# openSX70_WIP_NEW_LAYOUT_20171230_V32_man.net
KiCad netlist of a schematic drawn in EAGLE
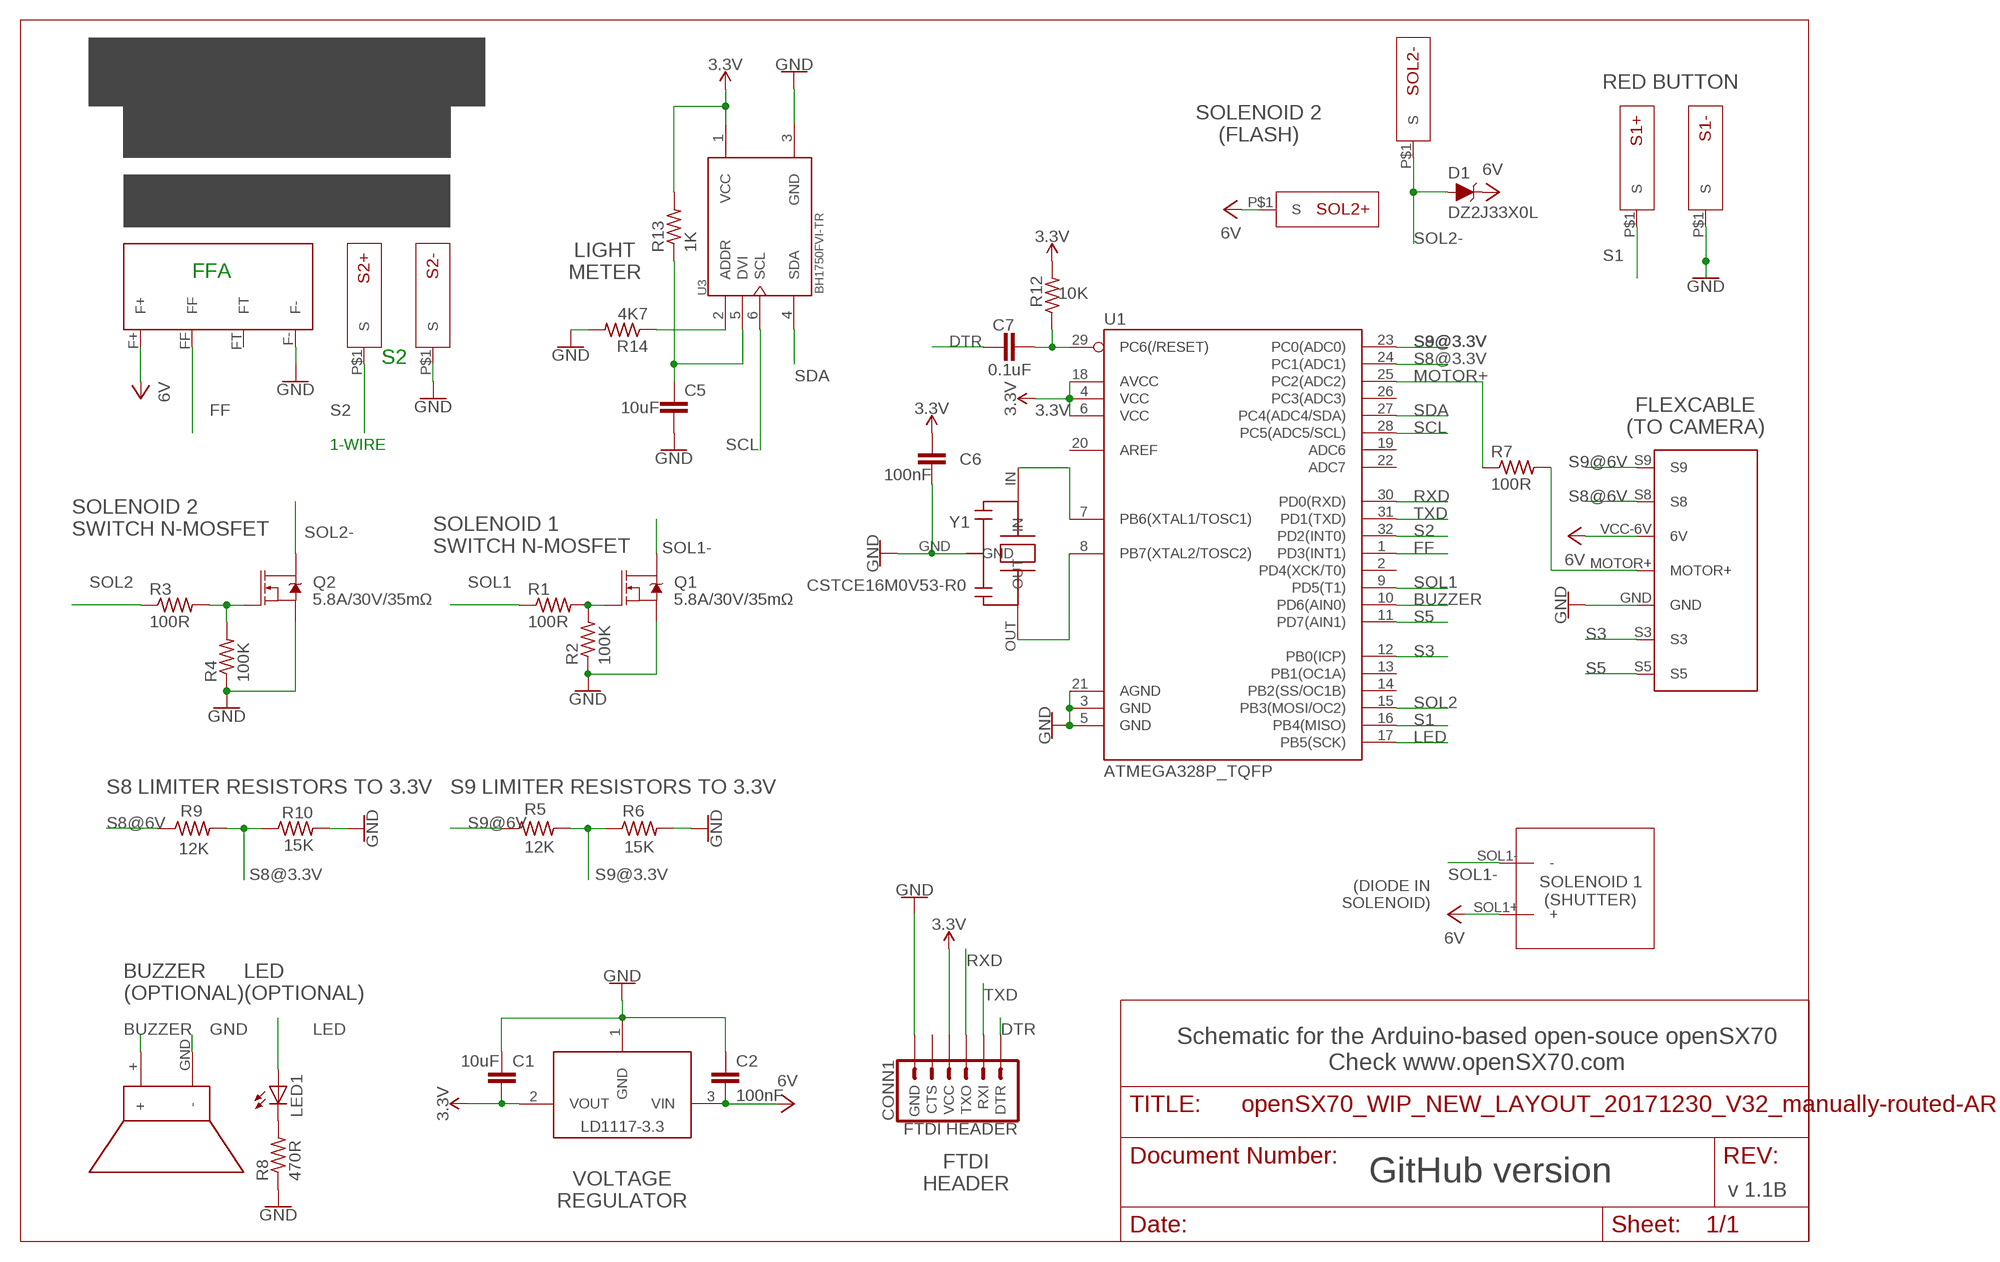
[diagram p0: schematic, sheet 1]

(export (version "E")
  (design (tool "Eeschema 10.0.6"))
  (components
    (comp (ref "BUZZ1")
      (value "CSET8-5G")
      (footprint "eagle-import:CSET8-5G_PACKAGE")
      (libsource (lib "eagle-import") (part "CSET8-5G"))
    )
    (comp (ref "C1")
      (value "10uF")
      (footprint "eagle-import:0603")
      (libsource (lib "eagle-import") (part "10UF-0603-6.3V-20%"))
    )
    (comp (ref "C2")
      (value "100nF")
      (footprint "eagle-import:C0603K")
      (libsource (lib "eagle-import") (part "C-EUC0603K"))
    )
    (comp (ref "C5")
      (value "10uF")
      (footprint "eagle-import:0603")
      (libsource (lib "eagle-import") (part "10UF-0603-6.3V-20%"))
    )
    (comp (ref "C6")
      (value "100nF")
      (footprint "eagle-import:C0805")
      (libsource (lib "eagle-import") (part "resistor_C-EUC0805"))
    )
    (comp (ref "C7")
      (value "0.1uF")
      (footprint "eagle-import:0603")
      (libsource (lib "eagle-import") (part "0.1UF-0603-25V-(+80/-20%)"))
    )
    (comp (ref "CONN1")
      (value "FTDI HEADER")
      (footprint "eagle-import:1X06")
      (libsource (lib "eagle-import") (part "6_PIN_SERIAL_TARGET"))
    )
    (comp (ref "D1")
      (value "DZ2J33X0L")
      (footprint "eagle-import:SMINI2")
      (libsource (lib "eagle-import") (part "DZ2J33X0L"))
    )
    (comp (ref "LD11173.3V")
      (value "LD1117 3.3V")
      (footprint "eagle-import:SOT223")
      (fields (field (name "MF") "Advanced Monolithic Systems") (field (name "MP") "AMS1117-5.0"))
      (libsource (lib "eagle-import") (part "LD1117-3.3"))
    )
    (comp (ref "LED1")
      (value "LEDCHIPLED_0805")
      (footprint "eagle-import:CHIPLED_0805")
      (libsource (lib "eagle-import") (part "LEDCHIPLED_0805"))
    )
    (comp (ref "Q1")
      (value "5.8A/30V/35mΩ")
      (footprint "eagle-import:SOT23-3")
      (libsource (lib "eagle-import") (part "MOSFET-NCH-AO3404A"))
    )
    (comp (ref "Q2")
      (value "5.8A/30V/35mΩ")
      (footprint "eagle-import:SOT23-3")
      (libsource (lib "eagle-import") (part "MOSFET-NCH-AO3404A"))
    )
    (comp (ref "R1")
      (value "100R")
      (footprint "eagle-import:R0603")
      (libsource (lib "eagle-import") (part "R-US_R0603"))
    )
    (comp (ref "R2")
      (value "100K")
      (footprint "eagle-import:R0603")
      (libsource (lib "eagle-import") (part "R-US_R0603"))
    )
    (comp (ref "R3")
      (value "100R")
      (footprint "eagle-import:R0603")
      (libsource (lib "eagle-import") (part "R-US_R0603"))
    )
    (comp (ref "R4")
      (value "100K")
      (footprint "eagle-import:R0603")
      (libsource (lib "eagle-import") (part "R-US_R0603"))
    )
    (comp (ref "R5")
      (value "12K")
      (footprint "eagle-import:R0603")
      (libsource (lib "eagle-import") (part "R-US_R0603"))
    )
    (comp (ref "R6")
      (value "15K")
      (footprint "eagle-import:R0603")
      (libsource (lib "eagle-import") (part "R-US_R0603"))
    )
    (comp (ref "R7")
      (value "100R")
      (footprint "eagle-import:R0603")
      (libsource (lib "eagle-import") (part "R-US_R0603"))
    )
    (comp (ref "R8")
      (value "470R")
      (footprint "eagle-import:R0603")
      (libsource (lib "eagle-import") (part "R-US_R0603"))
    )
    (comp (ref "R9")
      (value "12K")
      (footprint "eagle-import:R0603")
      (libsource (lib "eagle-import") (part "R-US_R0603"))
    )
    (comp (ref "R10")
      (value "15K")
      (footprint "eagle-import:R0603")
      (libsource (lib "eagle-import") (part "R-US_R0603"))
    )
    (comp (ref "R12")
      (value "10K")
      (footprint "eagle-import:R0603")
      (libsource (lib "eagle-import") (part "R-US_R0603"))
    )
    (comp (ref "R13")
      (value "1K")
      (footprint "eagle-import:R0603")
      (libsource (lib "eagle-import") (part "R-US_R0603"))
    )
    (comp (ref "R14")
      (value "4K7")
      (footprint "eagle-import:R0603")
      (libsource (lib "eagle-import") (part "R-US_R0603"))
    )
    (comp (ref "S1+")
      (value "SX70-S-PAD-NEW")
      (footprint "eagle-import:SX70-S-PAD2")
      (libsource (lib "eagle-import") (part "SX70-S-PAD-NEW"))
    )
    (comp (ref "S1-")
      (value "SX70-S-PAD-NEW")
      (footprint "eagle-import:SX70-S-PAD2")
      (libsource (lib "eagle-import") (part "SX70-S-PAD-NEW"))
    )
    (comp (ref "S2+")
      (value "SX70-S-PAD-NEW")
      (footprint "eagle-import:SX70-S-PAD2")
      (libsource (lib "eagle-import") (part "SX70-S-PAD-NEW"))
    )
    (comp (ref "S2-")
      (value "SX70-S-PAD-NEW")
      (footprint "eagle-import:SX70-S-PAD2")
      (libsource (lib "eagle-import") (part "SX70-S-PAD-NEW"))
    )
    (comp (ref "SOL1")
      (value "SX70-SOLENOID1-2PADS")
      (footprint "eagle-import:SX70-SOLENOID1-2")
      (libsource (lib "eagle-import") (part "SX70-SOLENOID1-2PADS"))
    )
    (comp (ref "SOL2+")
      (value "SX70-S-PAD-NEW")
      (footprint "eagle-import:SX70-S-PAD2")
      (libsource (lib "eagle-import") (part "SX70-S-PAD-NEW"))
    )
    (comp (ref "SOL2-")
      (value "SX70-S-PAD-NEW")
      (footprint "eagle-import:SX70-S-PAD2")
      (libsource (lib "eagle-import") (part "SX70-S-PAD-NEW"))
    )
    (comp (ref "U$1")
      (value "SX70-7-PAD")
      (footprint "eagle-import:SX70-7-PAD")
      (libsource (lib "eagle-import") (part "SX70-7-PAD"))
    )
    (comp (ref "U$2")
      (value "FFA")
      (footprint "eagle-import:FFA-PAD-PACKAGE")
      (libsource (lib "eagle-import") (part "SX70-FFA-PAD"))
    )
    (comp (ref "U1")
      (value "ATMEGA328P_TQFP")
      (footprint "eagle-import:TQFP32-08")
      (libsource (lib "eagle-import") (part "ATMEGA328P_TQFP"))
    )
    (comp (ref "U3")
      (value "BH1750FVI-TR")
      (footprint "eagle-import:SOTFL50P300X75-6N")
      (fields (field (name "MF") "Rohm"))
      (libsource (lib "eagle-import") (part "BH1750FVI-TR"))
    )
    (comp (ref "Y1")
      (value "CSTCE16M0V53-R0")
      (footprint "eagle-import:CFP95P160X100-3N")
      (fields (field (name "MF") "Murata"))
      (libsource (lib "eagle-import") (part "CSTCE16M0V53-R0"))
    )
  )
  (nets
    (net (code "1") (name "/BUZZER") (class "Default")
      (node (ref "BUZZ1") (pin "+") (pinfunction "+_+") (pintype "bidirectional"))
      (node (ref "U1") (pin "10") (pinfunction "PD6(AIN0)_10") (pintype "bidirectional"))
    )
    (net (code "2") (name "/DTR") (class "Default")
      (node (ref "C7") (pin "1") (pinfunction "1_1") (pintype "passive"))
      (node (ref "CONN1") (pin "1") (pinfunction "DTR_1") (pintype "passive"))
    )
    (net (code "3") (name "/FF") (class "Default")
      (node (ref "U$2") (pin "FF") (pinfunction "FF_FF") (pintype "bidirectional"))
      (node (ref "U1") (pin "1") (pinfunction "PD3(INT1)_1") (pintype "bidirectional"))
    )
    (net (code "4") (name "/LED") (class "Default")
      (node (ref "LED1") (pin "A") (pinfunction "A_A") (pintype "passive"))
      (node (ref "U1") (pin "17") (pinfunction "PB5(SCK)_17") (pintype "bidirectional"))
    )
    (net (code "5") (name "/MOTOR+") (class "Default")
      (node (ref "R7") (pin "1") (pinfunction "1_1") (pintype "passive"))
      (node (ref "U1") (pin "25") (pinfunction "PC2(ADC2)_25") (pintype "bidirectional"))
    )
    (net (code "6") (name "/RXD") (class "Default")
      (node (ref "CONN1") (pin "3") (pinfunction "TXO_3") (pintype "passive"))
      (node (ref "U1") (pin "30") (pinfunction "PD0(RXD)_30") (pintype "bidirectional"))
    )
    (net (code "7") (name "/S1") (class "Default")
      (node (ref "S1+") (pin "P$1") (pinfunction "S_P$1") (pintype "bidirectional"))
      (node (ref "U1") (pin "16") (pinfunction "PB4(MISO)_16") (pintype "bidirectional"))
    )
    (net (code "8") (name "/S2") (class "Default")
      (node (ref "S2+") (pin "P$1") (pinfunction "S_P$1") (pintype "bidirectional"))
      (node (ref "U1") (pin "32") (pinfunction "PD2(INT0)_32") (pintype "bidirectional"))
    )
    (net (code "9") (name "/S3") (class "Default")
      (node (ref "U$1") (pin "S3") (pinfunction "S3_S3") (pintype "bidirectional"))
      (node (ref "U1") (pin "12") (pinfunction "PB0(ICP)_12") (pintype "bidirectional"))
    )
    (net (code "10") (name "/S5") (class "Default")
      (node (ref "U$1") (pin "S5") (pinfunction "S5_S5") (pintype "bidirectional"))
      (node (ref "U1") (pin "11") (pinfunction "PD7(AIN1)_11") (pintype "bidirectional"))
    )
    (net (code "11") (name "/S8@3.3V") (class "Default")
      (node (ref "R10") (pin "1") (pinfunction "1_1") (pintype "passive"))
      (node (ref "R9") (pin "2") (pinfunction "2_2") (pintype "passive"))
      (node (ref "U1") (pin "24") (pinfunction "PC1(ADC1)_24") (pintype "bidirectional"))
    )
    (net (code "12") (name "/S8@6V") (class "Default")
      (node (ref "R9") (pin "1") (pinfunction "1_1") (pintype "passive"))
      (node (ref "U$1") (pin "S8") (pinfunction "S8_S8") (pintype "bidirectional"))
    )
    (net (code "13") (name "/S9@3.3V") (class "Default")
      (node (ref "R5") (pin "2") (pinfunction "2_2") (pintype "passive"))
      (node (ref "R6") (pin "1") (pinfunction "1_1") (pintype "passive"))
      (node (ref "U1") (pin "23") (pinfunction "PC0(ADC0)_23") (pintype "bidirectional"))
    )
    (net (code "14") (name "/S9@6V") (class "Default")
      (node (ref "R5") (pin "1") (pinfunction "1_1") (pintype "passive"))
      (node (ref "U$1") (pin "S9") (pinfunction "S9_S9") (pintype "bidirectional"))
    )
    (net (code "15") (name "/SCL") (class "Default")
      (node (ref "U1") (pin "28") (pinfunction "PC5(ADC5/SCL)_28") (pintype "bidirectional"))
      (node (ref "U3") (pin "6") (pinfunction "SCL_6") (pintype "input"))
    )
    (net (code "16") (name "/SDA") (class "Default")
      (node (ref "U1") (pin "27") (pinfunction "PC4(ADC4/SDA)_27") (pintype "bidirectional"))
      (node (ref "U3") (pin "4") (pinfunction "SDA_4") (pintype "bidirectional"))
    )
    (net (code "17") (name "/SOL1") (class "Default")
      (node (ref "R1") (pin "1") (pinfunction "1_1") (pintype "passive"))
      (node (ref "U1") (pin "9") (pinfunction "PD5(T1)_9") (pintype "bidirectional"))
    )
    (net (code "18") (name "/SOL1-") (class "Default")
      (node (ref "Q1") (pin "3") (pinfunction "D_3") (pintype "bidirectional"))
      (node (ref "SOL1") (pin "SOL1-") (pinfunction "-_SOL1-") (pintype "bidirectional"))
    )
    (net (code "19") (name "/SOL2") (class "Default")
      (node (ref "R3") (pin "1") (pinfunction "1_1") (pintype "passive"))
      (node (ref "U1") (pin "15") (pinfunction "PB3(MOSI/OC2)_15") (pintype "bidirectional"))
    )
    (net (code "20") (name "/SOL2-") (class "Default")
      (node (ref "D1") (pin "P$2") (pinfunction "A_P$2") (pintype "passive"))
      (node (ref "Q2") (pin "3") (pinfunction "D_3") (pintype "bidirectional"))
      (node (ref "SOL2-") (pin "P$1") (pinfunction "S_P$1") (pintype "bidirectional"))
    )
    (net (code "21") (name "/TXD") (class "Default")
      (node (ref "CONN1") (pin "2") (pinfunction "RXI_2") (pintype "passive"))
      (node (ref "U1") (pin "31") (pinfunction "PD1(TXD)_31") (pintype "bidirectional"))
    )
    (net (code "22") (name "3.3V") (class "Default")
      (node (ref "C1") (pin "2") (pinfunction "2_2") (pintype "passive"))
      (node (ref "C6") (pin "1") (pinfunction "1_1") (pintype "passive"))
      (node (ref "CONN1") (pin "4") (pinfunction "VCC_4") (pintype "passive"))
      (node (ref "LD11173.3V") (pin "2") (pinfunction "VOUT_2") (pintype "bidirectional"))
      (node (ref "R12") (pin "2") (pinfunction "2_2") (pintype "passive"))
      (node (ref "R13") (pin "2") (pinfunction "2_2") (pintype "passive"))
      (node (ref "U1") (pin "18") (pinfunction "AVCC_18") (pintype "bidirectional"))
      (node (ref "U1") (pin "4") (pinfunction "VCC_4") (pintype "bidirectional"))
      (node (ref "U1") (pin "6") (pinfunction "VCC_6") (pintype "bidirectional"))
      (node (ref "U3") (pin "1") (pinfunction "VCC_1") (pintype "power_in"))
    )
    (net (code "23") (name "6V") (class "Default")
      (node (ref "C2") (pin "2") (pinfunction "2_2") (pintype "passive"))
      (node (ref "D1") (pin "P$1") (pinfunction "C_P$1") (pintype "passive"))
      (node (ref "LD11173.3V") (pin "3") (pinfunction "VIN_3") (pintype "bidirectional"))
      (node (ref "SOL1") (pin "SOL1+") (pinfunction "+_SOL1+") (pintype "bidirectional"))
      (node (ref "SOL2+") (pin "P$1") (pinfunction "S_P$1") (pintype "bidirectional"))
      (node (ref "U$1") (pin "VCC-6V") (pinfunction "6V_VCC-6V") (pintype "bidirectional"))
      (node (ref "U$2") (pin "F+") (pinfunction "F+_F+") (pintype "bidirectional"))
    )
    (net (code "24") (name "GND") (class "Default")
      (node (ref "BUZZ1") (pin "GND") (pinfunction "-_GND") (pintype "bidirectional"))
      (node (ref "C1") (pin "1") (pinfunction "1_1") (pintype "passive"))
      (node (ref "C2") (pin "1") (pinfunction "1_1") (pintype "passive"))
      (node (ref "C5") (pin "2") (pinfunction "2_2") (pintype "passive"))
      (node (ref "C6") (pin "2") (pinfunction "2_2") (pintype "passive"))
      (node (ref "CONN1") (pin "6") (pinfunction "GND_6") (pintype "passive"))
      (node (ref "LD11173.3V") (pin "1") (pinfunction "GND_1") (pintype "bidirectional"))
      (node (ref "Q1") (pin "2") (pinfunction "S_2") (pintype "bidirectional"))
      (node (ref "Q2") (pin "2") (pinfunction "S_2") (pintype "bidirectional"))
      (node (ref "R10") (pin "2") (pinfunction "2_2") (pintype "passive"))
      (node (ref "R14") (pin "2") (pinfunction "2_2") (pintype "passive"))
      (node (ref "R2") (pin "1") (pinfunction "1_1") (pintype "passive"))
      (node (ref "R4") (pin "1") (pinfunction "1_1") (pintype "passive"))
      (node (ref "R6") (pin "2") (pinfunction "2_2") (pintype "passive"))
      (node (ref "R8") (pin "1") (pinfunction "1_1") (pintype "passive"))
      (node (ref "S1-") (pin "P$1") (pinfunction "S_P$1") (pintype "bidirectional"))
      (node (ref "S2-") (pin "P$1") (pinfunction "S_P$1") (pintype "bidirectional"))
      (node (ref "U$1") (pin "GND") (pinfunction "GND_GND") (pintype "bidirectional"))
      (node (ref "U$2") (pin "F-") (pinfunction "F-_F-") (pintype "bidirectional"))
      (node (ref "U1") (pin "21") (pinfunction "AGND_21") (pintype "bidirectional"))
      (node (ref "U1") (pin "3") (pinfunction "GND_3") (pintype "bidirectional"))
      (node (ref "U1") (pin "5") (pinfunction "GND_5") (pintype "bidirectional"))
      (node (ref "U3") (pin "3") (pinfunction "GND_3") (pintype "power_in"))
      (node (ref "Y1") (pin "GND") (pinfunction "GND_GND") (pintype "passive"))
    )
    (net (code "25") (name "Net-(LED1-PadC)") (class "Default")
      (node (ref "LED1") (pin "C") (pinfunction "C_C") (pintype "passive"))
      (node (ref "R8") (pin "2") (pinfunction "2_2") (pintype "passive"))
    )
    (net (code "26") (name "Net-(Q1-G)") (class "Default")
      (node (ref "Q1") (pin "1") (pinfunction "G_1") (pintype "bidirectional"))
      (node (ref "R1") (pin "2") (pinfunction "2_2") (pintype "passive"))
      (node (ref "R2") (pin "2") (pinfunction "2_2") (pintype "passive"))
    )
    (net (code "27") (name "Net-(Q2-G)") (class "Default")
      (node (ref "Q2") (pin "1") (pinfunction "G_1") (pintype "bidirectional"))
      (node (ref "R3") (pin "2") (pinfunction "2_2") (pintype "passive"))
      (node (ref "R4") (pin "2") (pinfunction "2_2") (pintype "passive"))
    )
    (net (code "28") (name "Net-(R7-Pad2)") (class "Default")
      (node (ref "R7") (pin "2") (pinfunction "2_2") (pintype "passive"))
      (node (ref "U$1") (pin "MOTOR+") (pinfunction "MOTOR+_MOTOR+") (pintype "bidirectional"))
    )
    (net (code "29") (name "Net-(U1-PB6(XTAL1{slash}TOSC1))") (class "Default")
      (node (ref "U1") (pin "7") (pinfunction "PB6(XTAL1/TOSC1)_7") (pintype "bidirectional"))
      (node (ref "Y1") (pin "IN") (pinfunction "IN_IN") (pintype "input"))
    )
    (net (code "30") (name "Net-(U1-PB7(XTAL2{slash}TOSC2))") (class "Default")
      (node (ref "U1") (pin "8") (pinfunction "PB7(XTAL2/TOSC2)_8") (pintype "bidirectional"))
      (node (ref "Y1") (pin "OUT") (pinfunction "OUT_OUT") (pintype "output"))
    )
    (net (code "31") (name "Net-(U1-PC6({slash}RESET))") (class "Default")
      (node (ref "C7") (pin "2") (pinfunction "2_2") (pintype "passive"))
      (node (ref "R12") (pin "1") (pinfunction "1_1") (pintype "passive"))
      (node (ref "U1") (pin "29") (pinfunction "PC6(/RESET)_29") (pintype "bidirectional"))
    )
    (net (code "32") (name "Net-(U3-ADDR)") (class "Default")
      (node (ref "R14") (pin "1") (pinfunction "1_1") (pintype "passive"))
      (node (ref "U3") (pin "2") (pinfunction "ADDR_2") (pintype "input"))
    )
    (net (code "33") (name "Net-(U3-DVI)") (class "Default")
      (node (ref "C5") (pin "1") (pinfunction "1_1") (pintype "passive"))
      (node (ref "R13") (pin "1") (pinfunction "1_1") (pintype "passive"))
      (node (ref "U3") (pin "5") (pinfunction "DVI_5") (pintype "input"))
    )
    (net (code "34") (name "unconnected-(CONN1-CTS-Pad5)") (class "Default")
      (node (ref "CONN1") (pin "5") (pinfunction "CTS_5") (pintype "passive"))
    )
    (net (code "35") (name "unconnected-(U$2-PadFT)") (class "Default")
      (node (ref "U$2") (pin "FT") (pinfunction "FT_FT") (pintype "bidirectional"))
    )
    (net (code "36") (name "unconnected-(U1-ADC6-Pad19)") (class "Default")
      (node (ref "U1") (pin "19") (pinfunction "ADC6_19") (pintype "bidirectional"))
    )
    (net (code "37") (name "unconnected-(U1-ADC7-Pad22)") (class "Default")
      (node (ref "U1") (pin "22") (pinfunction "ADC7_22") (pintype "bidirectional"))
    )
    (net (code "38") (name "unconnected-(U1-AREF-Pad20)") (class "Default")
      (node (ref "U1") (pin "20") (pinfunction "AREF_20") (pintype "bidirectional"))
    )
    (net (code "39") (name "unconnected-(U1-PB1(OC1A)-Pad13)") (class "Default")
      (node (ref "U1") (pin "13") (pinfunction "PB1(OC1A)_13") (pintype "bidirectional"))
    )
    (net (code "40") (name "unconnected-(U1-PB2(SS{slash}OC1B)-Pad14)") (class "Default")
      (node (ref "U1") (pin "14") (pinfunction "PB2(SS/OC1B)_14") (pintype "bidirectional"))
    )
    (net (code "41") (name "unconnected-(U1-PC3(ADC3)-Pad26)") (class "Default")
      (node (ref "U1") (pin "26") (pinfunction "PC3(ADC3)_26") (pintype "bidirectional"))
    )
    (net (code "42") (name "unconnected-(U1-PD4(XCK{slash}T0)-Pad2)") (class "Default")
      (node (ref "U1") (pin "2") (pinfunction "PD4(XCK/T0)_2") (pintype "bidirectional"))
    )
  )
)
